# RoverMux.net
KiCad netlist of a schematic drawn in EAGLE
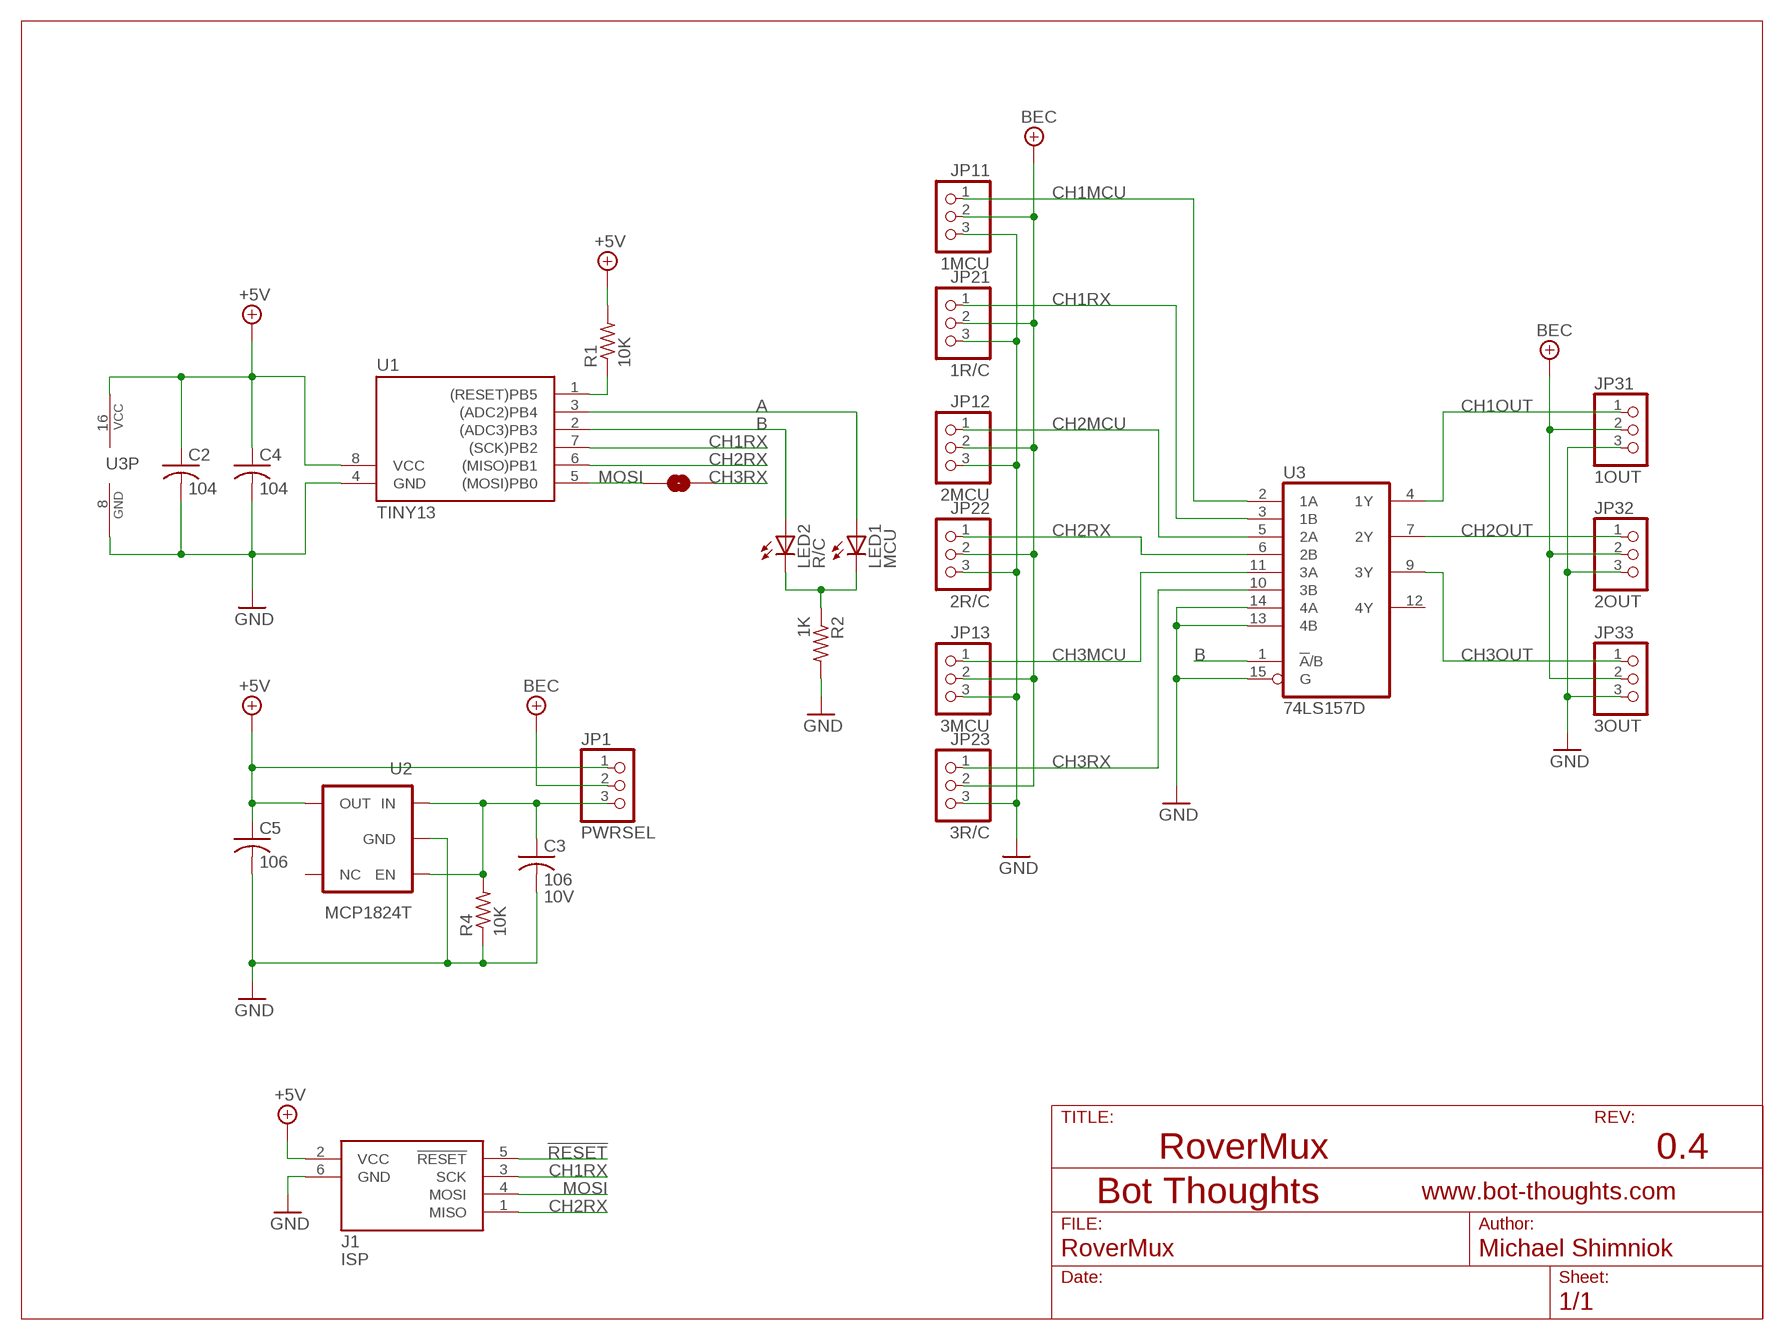
[diagram p0: schematic, sheet 1]

(export (version "E")
  (design (tool "Eeschema 10.0.6"))
  (components
    (comp (ref "C2")
      (value "104")
      (footprint "eagle-import:C0603")
      (fields (field (name "PARTNO") "C1608X7R1E104K080AA"))
      (libsource (lib "eagle-import") (part "C-USC0603"))
    )
    (comp (ref "C3")
      (value "106")
      (footprint "eagle-import:C0603")
      (fields (field (name "PARTNO") "CL10A106MP8NNNC") (field (name "VOLTAGE") "10V"))
      (libsource (lib "eagle-import") (part "C-USC0603"))
    )
    (comp (ref "C4")
      (value "104")
      (footprint "eagle-import:C0603")
      (fields (field (name "PARTNO") "C1608X7R1E104K080AA"))
      (libsource (lib "eagle-import") (part "C-USC0603"))
    )
    (comp (ref "C5")
      (value "106")
      (footprint "eagle-import:C0603")
      (fields (field (name "PARTNO") "CL10A106MP8NNNC"))
      (libsource (lib "eagle-import") (part "C-USC0603"))
    )
    (comp (ref "J1")
      (value "ISP")
      (footprint "eagle-import:CON6P2R")
      (libsource (lib "eagle-import") (part "AVRISP6"))
    )
    (comp (ref "JP1")
      (value "PWRSEL")
      (footprint "eagle-import:1X03M")
      (libsource (lib "eagle-import") (part "PINHD-1X03_2.00"))
    )
    (comp (ref "JP11")
      (value "1MCU")
      (footprint "eagle-import:1X03-S")
      (libsource (lib "eagle-import") (part "PINHD-1X03_2.54-S"))
    )
    (comp (ref "JP12")
      (value "2MCU")
      (footprint "eagle-import:1X03-S")
      (libsource (lib "eagle-import") (part "PINHD-1X03_2.54-S"))
    )
    (comp (ref "JP13")
      (value "3MCU")
      (footprint "eagle-import:1X03-S")
      (libsource (lib "eagle-import") (part "PINHD-1X03_2.54-S"))
    )
    (comp (ref "JP21")
      (value "1R/C")
      (footprint "eagle-import:1X03-S")
      (libsource (lib "eagle-import") (part "PINHD-1X03_2.54-S"))
    )
    (comp (ref "JP22")
      (value "2R/C")
      (footprint "eagle-import:1X03-S")
      (libsource (lib "eagle-import") (part "PINHD-1X03_2.54-S"))
    )
    (comp (ref "JP23")
      (value "3R/C")
      (footprint "eagle-import:1X03-S")
      (libsource (lib "eagle-import") (part "PINHD-1X03_2.54-S"))
    )
    (comp (ref "JP31")
      (value "1OUT")
      (footprint "eagle-import:1X03-S")
      (libsource (lib "eagle-import") (part "PINHD-1X03_2.54-S"))
    )
    (comp (ref "JP32")
      (value "2OUT")
      (footprint "eagle-import:1X03-S")
      (libsource (lib "eagle-import") (part "PINHD-1X03_2.54-S"))
    )
    (comp (ref "JP33")
      (value "3OUT")
      (footprint "eagle-import:1X03-S")
      (libsource (lib "eagle-import") (part "PINHD-1X03_2.54-S"))
    )
    (comp (ref "LED1")
      (value "MCU")
      (footprint "eagle-import:CHIPLED_1206")
      (fields (field (name "PARTNO") "LH N974-KN-1"))
      (libsource (lib "eagle-import") (part "LEDCHIPLED_1206"))
    )
    (comp (ref "LED2")
      (value "R/C")
      (footprint "eagle-import:CHIPLED_1206")
      (fields (field (name "PARTNO") "LG N971-KN-1"))
      (libsource (lib "eagle-import") (part "LEDCHIPLED_1206"))
    )
    (comp (ref "R1")
      (value "10K")
      (footprint "eagle-import:R0603")
      (fields (field (name "PARTNO") "1622829-1"))
      (libsource (lib "eagle-import") (part "R-US_R0603"))
    )
    (comp (ref "R2")
      (value "1K")
      (footprint "eagle-import:R0603")
      (fields (field (name "PARTNO") "RC0603JR-07330RL"))
      (libsource (lib "eagle-import") (part "R-US_R0603"))
    )
    (comp (ref "R4")
      (value "10K")
      (footprint "eagle-import:R0603")
      (fields (field (name "PARTNO") "1622829-1"))
      (libsource (lib "eagle-import") (part "R-US_R0603"))
    )
    (comp (ref "SJ1")
      (value "CH3")
      (footprint "eagle-import:SJ_2S-NOTRACE")
      (libsource (lib "eagle-import") (part "SOLDERJUMPERNC2"))
    )
    (comp (ref "U1")
      (value "TINY13")
      (footprint "eagle-import:SO08")
      (fields (field (name "PARTNO") "ATTINY13A-SSH"))
      (libsource (lib "eagle-import") (part "TINY138S2"))
    )
    (comp (ref "U2")
      (value "MCP1824T")
      (footprint "eagle-import:SOT23-5")
      (fields (field (name "PARTNO") "MCP1824T-5002E/OT"))
      (libsource (lib "eagle-import") (part "MCP1801"))
    )
    (comp (ref "U3")
      (value "74LS157D")
      (footprint "eagle-import:SO16")
      (fields (field (name "PARTNO") "74HCT157D,652"))
      (libsource (lib "eagle-import") (part "74157DLS"))
    )
  )
  (nets
    (net (code "1") (name "+5V") (class "Default")
      (node (ref "C2") (pin "1") (pinfunction "1_1") (pintype "passive"))
      (node (ref "C4") (pin "1") (pinfunction "1_1") (pintype "passive"))
      (node (ref "C5") (pin "1") (pinfunction "1_1") (pintype "passive"))
      (node (ref "J1") (pin "2") (pinfunction "VCC_2") (pintype "power_in"))
      (node (ref "JP1") (pin "1") (pinfunction "1_1") (pintype "passive"))
      (node (ref "R1") (pin "2") (pinfunction "2_2") (pintype "passive"))
      (node (ref "U1") (pin "8") (pinfunction "VCC_8") (pintype "power_in"))
      (node (ref "U2") (pin "5") (pinfunction "OUT_5") (pintype "passive"))
      (node (ref "U3") (pin "16") (pinfunction "VCC_16") (pintype "power_in"))
    )
    (net (code "2") (name "/A") (class "Default")
      (node (ref "LED1") (pin "A") (pinfunction "A_A") (pintype "passive"))
      (node (ref "U1") (pin "3") (pinfunction "(ADC2)PB4_3") (pintype "bidirectional"))
    )
    (net (code "3") (name "/B") (class "Default")
      (node (ref "LED2") (pin "A") (pinfunction "A_A") (pintype "passive"))
      (node (ref "U1") (pin "2") (pinfunction "(ADC3)PB3_2") (pintype "bidirectional"))
      (node (ref "U3") (pin "1") (pinfunction "~{A}/B_1") (pintype "input"))
    )
    (net (code "4") (name "/CH1MCU") (class "Default")
      (node (ref "JP11") (pin "1") (pinfunction "1_1") (pintype "passive"))
      (node (ref "U3") (pin "2") (pinfunction "1A_2") (pintype "input"))
    )
    (net (code "5") (name "/CH1OUT") (class "Default")
      (node (ref "JP31") (pin "1") (pinfunction "1_1") (pintype "passive"))
      (node (ref "U3") (pin "4") (pinfunction "1Y_4") (pintype "output"))
    )
    (net (code "6") (name "/CH1RX") (class "Default")
      (node (ref "J1") (pin "3") (pinfunction "SCK_3") (pintype "output"))
      (node (ref "JP21") (pin "1") (pinfunction "1_1") (pintype "passive"))
      (node (ref "U1") (pin "7") (pinfunction "(SCK)PB2_7") (pintype "bidirectional"))
      (node (ref "U3") (pin "3") (pinfunction "1B_3") (pintype "input"))
    )
    (net (code "7") (name "/CH2MCU") (class "Default")
      (node (ref "JP12") (pin "1") (pinfunction "1_1") (pintype "passive"))
      (node (ref "U3") (pin "5") (pinfunction "2A_5") (pintype "input"))
    )
    (net (code "8") (name "/CH2OUT") (class "Default")
      (node (ref "JP32") (pin "1") (pinfunction "1_1") (pintype "passive"))
      (node (ref "U3") (pin "7") (pinfunction "2Y_7") (pintype "output"))
    )
    (net (code "9") (name "/CH2RX") (class "Default")
      (node (ref "J1") (pin "1") (pinfunction "MISO_1") (pintype "input"))
      (node (ref "JP22") (pin "1") (pinfunction "1_1") (pintype "passive"))
      (node (ref "U1") (pin "6") (pinfunction "(MISO)PB1_6") (pintype "bidirectional"))
      (node (ref "U3") (pin "6") (pinfunction "2B_6") (pintype "input"))
    )
    (net (code "10") (name "/CH3MCU") (class "Default")
      (node (ref "JP13") (pin "1") (pinfunction "1_1") (pintype "passive"))
      (node (ref "U3") (pin "11") (pinfunction "3A_11") (pintype "input"))
    )
    (net (code "11") (name "/CH3OUT") (class "Default")
      (node (ref "JP33") (pin "1") (pinfunction "1_1") (pintype "passive"))
      (node (ref "U3") (pin "9") (pinfunction "3Y_9") (pintype "output"))
    )
    (net (code "12") (name "/CH3RX") (class "Default")
      (node (ref "JP23") (pin "1") (pinfunction "1_1") (pintype "passive"))
      (node (ref "SJ1") (pin "2") (pinfunction "2_2") (pintype "passive"))
      (node (ref "U3") (pin "10") (pinfunction "3B_10") (pintype "input"))
    )
    (net (code "13") (name "/MOSI") (class "Default")
      (node (ref "J1") (pin "4") (pinfunction "MOSI_4") (pintype "output"))
      (node (ref "SJ1") (pin "1") (pinfunction "1_1") (pintype "passive"))
      (node (ref "U1") (pin "5") (pinfunction "(MOSI)PB0_5") (pintype "bidirectional"))
    )
    (net (code "14") (name "/~{RESET}") (class "Default")
      (node (ref "J1") (pin "5") (pinfunction "~{RESET}_5") (pintype "output"))
      (node (ref "R1") (pin "1") (pinfunction "1_1") (pintype "passive"))
      (node (ref "U1") (pin "1") (pinfunction "(RESET)PB5_1") (pintype "bidirectional"))
    )
    (net (code "15") (name "BEC") (class "Default")
      (node (ref "JP1") (pin "2") (pinfunction "2_2") (pintype "passive"))
      (node (ref "JP11") (pin "2") (pinfunction "2_2") (pintype "passive"))
      (node (ref "JP12") (pin "2") (pinfunction "2_2") (pintype "passive"))
      (node (ref "JP13") (pin "2") (pinfunction "2_2") (pintype "passive"))
      (node (ref "JP21") (pin "2") (pinfunction "2_2") (pintype "passive"))
      (node (ref "JP22") (pin "2") (pinfunction "2_2") (pintype "passive"))
      (node (ref "JP23") (pin "2") (pinfunction "2_2") (pintype "passive"))
      (node (ref "JP31") (pin "2") (pinfunction "2_2") (pintype "passive"))
      (node (ref "JP32") (pin "2") (pinfunction "2_2") (pintype "passive"))
      (node (ref "JP33") (pin "2") (pinfunction "2_2") (pintype "passive"))
    )
    (net (code "16") (name "GND") (class "Default")
      (node (ref "C2") (pin "2") (pinfunction "2_2") (pintype "passive"))
      (node (ref "C3") (pin "2") (pinfunction "2_2") (pintype "passive"))
      (node (ref "C4") (pin "2") (pinfunction "2_2") (pintype "passive"))
      (node (ref "C5") (pin "2") (pinfunction "2_2") (pintype "passive"))
      (node (ref "J1") (pin "6") (pinfunction "GND_6") (pintype "power_in"))
      (node (ref "JP11") (pin "3") (pinfunction "3_3") (pintype "passive"))
      (node (ref "JP12") (pin "3") (pinfunction "3_3") (pintype "passive"))
      (node (ref "JP13") (pin "3") (pinfunction "3_3") (pintype "passive"))
      (node (ref "JP21") (pin "3") (pinfunction "3_3") (pintype "passive"))
      (node (ref "JP22") (pin "3") (pinfunction "3_3") (pintype "passive"))
      (node (ref "JP23") (pin "3") (pinfunction "3_3") (pintype "passive"))
      (node (ref "JP31") (pin "3") (pinfunction "3_3") (pintype "passive"))
      (node (ref "JP32") (pin "3") (pinfunction "3_3") (pintype "passive"))
      (node (ref "JP33") (pin "3") (pinfunction "3_3") (pintype "passive"))
      (node (ref "R2") (pin "2") (pinfunction "2_2") (pintype "passive"))
      (node (ref "R4") (pin "1") (pinfunction "1_1") (pintype "passive"))
      (node (ref "U1") (pin "4") (pinfunction "GND_4") (pintype "power_in"))
      (node (ref "U2") (pin "2") (pinfunction "GND_2") (pintype "input"))
      (node (ref "U3") (pin "13") (pinfunction "4B_13") (pintype "input"))
      (node (ref "U3") (pin "14") (pinfunction "4A_14") (pintype "input"))
      (node (ref "U3") (pin "15") (pinfunction "G_15") (pintype "input"))
      (node (ref "U3") (pin "8") (pinfunction "GND_8") (pintype "power_in"))
    )
    (net (code "17") (name "Net-(LED1-PadC)") (class "Default")
      (node (ref "LED1") (pin "C") (pinfunction "C_C") (pintype "passive"))
      (node (ref "LED2") (pin "C") (pinfunction "C_C") (pintype "passive"))
      (node (ref "R2") (pin "1") (pinfunction "1_1") (pintype "passive"))
    )
    (net (code "18") (name "Net-(U2-EN)") (class "Default")
      (node (ref "C3") (pin "1") (pinfunction "1_1") (pintype "passive"))
      (node (ref "JP1") (pin "3") (pinfunction "3_3") (pintype "passive"))
      (node (ref "R4") (pin "2") (pinfunction "2_2") (pintype "passive"))
      (node (ref "U2") (pin "1") (pinfunction "IN_1") (pintype "input"))
      (node (ref "U2") (pin "3") (pinfunction "EN_3") (pintype "input"))
    )
    (net (code "19") (name "unconnected-(U2-NC-Pad4)") (class "Default")
      (node (ref "U2") (pin "4") (pinfunction "NC_4") (pintype "input"))
    )
    (net (code "20") (name "unconnected-(U3A-4Y-Pad12)") (class "Default")
      (node (ref "U3") (pin "12") (pinfunction "4Y_12") (pintype "output"))
    )
  )
)
